# adc.net
KiCad netlist of a schematic drawn in EAGLE
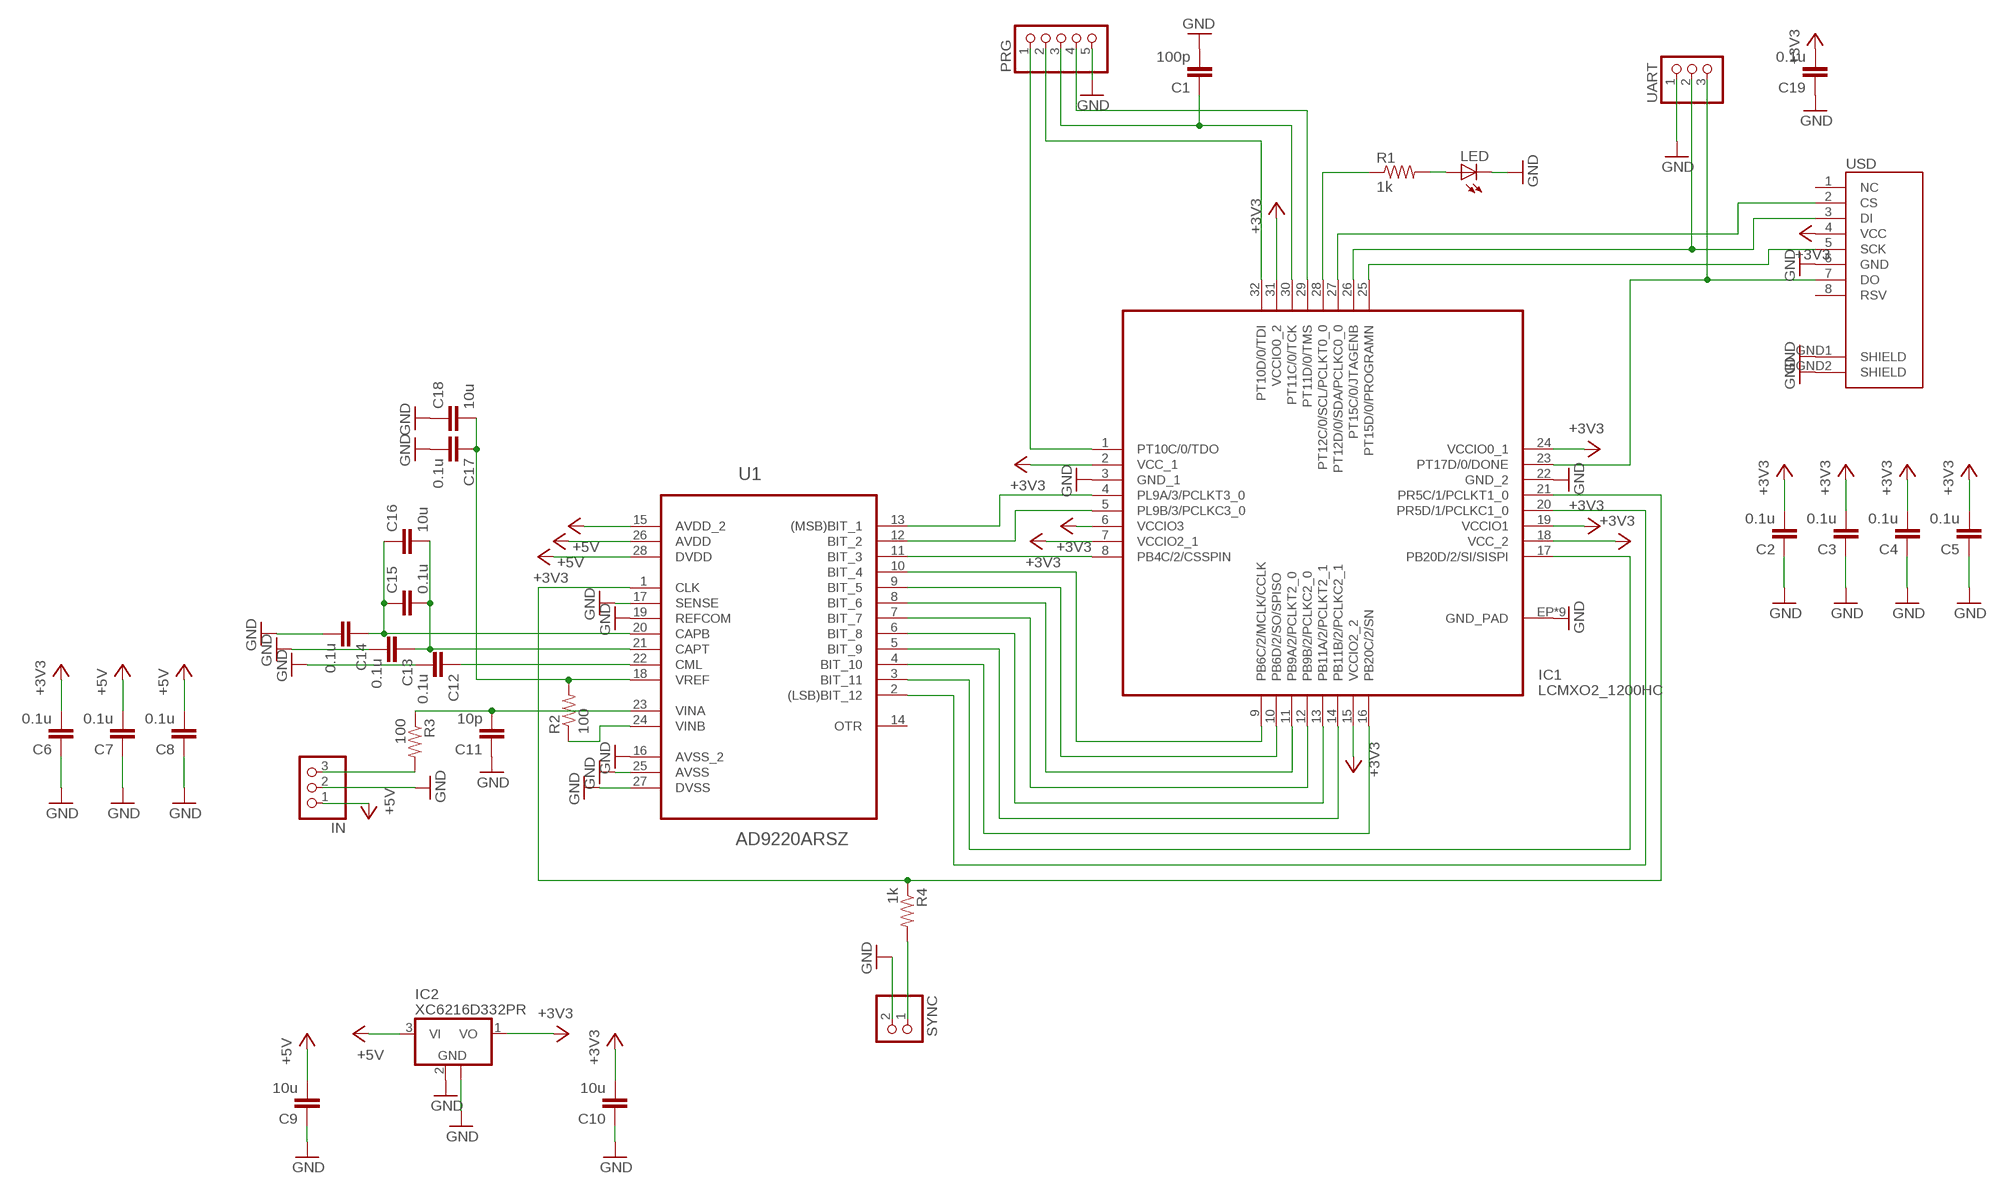
[diagram p0: schematic, sheet 1]

(export (version "E")
  (design (tool "Eeschema 10.0.6"))
  (components
    (comp (ref "C1")
      (value "100p")
      (footprint "eagle-import:C0603")
      (libsource (lib "eagle-import") (part "C-EUC0603"))
    )
    (comp (ref "C2")
      (value "0.1u")
      (footprint "eagle-import:C0603")
      (libsource (lib "eagle-import") (part "C-EUC0603"))
    )
    (comp (ref "C3")
      (value "0.1u")
      (footprint "eagle-import:C0603")
      (libsource (lib "eagle-import") (part "C-EUC0603"))
    )
    (comp (ref "C4")
      (value "0.1u")
      (footprint "eagle-import:C0603")
      (libsource (lib "eagle-import") (part "C-EUC0603"))
    )
    (comp (ref "C5")
      (value "0.1u")
      (footprint "eagle-import:C0603")
      (libsource (lib "eagle-import") (part "C-EUC0603"))
    )
    (comp (ref "C6")
      (value "0.1u")
      (footprint "eagle-import:C0603")
      (libsource (lib "eagle-import") (part "C-EUC0603"))
    )
    (comp (ref "C7")
      (value "0.1u")
      (footprint "eagle-import:C0603")
      (libsource (lib "eagle-import") (part "C-EUC0603"))
    )
    (comp (ref "C8")
      (value "0.1u")
      (footprint "eagle-import:C0603")
      (libsource (lib "eagle-import") (part "C-EUC0603"))
    )
    (comp (ref "C9")
      (value "10u")
      (footprint "eagle-import:C1206")
      (libsource (lib "eagle-import") (part "C-EUC1206"))
    )
    (comp (ref "C10")
      (value "10u")
      (footprint "eagle-import:C1206")
      (libsource (lib "eagle-import") (part "C-EUC1206"))
    )
    (comp (ref "C11")
      (value "10p")
      (footprint "eagle-import:C0603")
      (libsource (lib "eagle-import") (part "C-EUC0603"))
    )
    (comp (ref "C12")
      (value "0.1u")
      (footprint "eagle-import:C0603")
      (libsource (lib "eagle-import") (part "C-EUC0603"))
    )
    (comp (ref "C13")
      (value "0.1u")
      (footprint "eagle-import:C0603")
      (libsource (lib "eagle-import") (part "C-EUC0603"))
    )
    (comp (ref "C14")
      (value "0.1u")
      (footprint "eagle-import:C0603")
      (libsource (lib "eagle-import") (part "C-EUC0603"))
    )
    (comp (ref "C15")
      (value "0.1u")
      (footprint "eagle-import:C0603")
      (libsource (lib "eagle-import") (part "C-EUC0603"))
    )
    (comp (ref "C16")
      (value "10u")
      (footprint "eagle-import:C1206")
      (libsource (lib "eagle-import") (part "C-EUC1206"))
    )
    (comp (ref "C17")
      (value "0.1u")
      (footprint "eagle-import:C0603")
      (libsource (lib "eagle-import") (part "C-EUC0603"))
    )
    (comp (ref "C18")
      (value "10u")
      (footprint "eagle-import:C1206")
      (libsource (lib "eagle-import") (part "C-EUC1206"))
    )
    (comp (ref "C19")
      (value "0.1u")
      (footprint "eagle-import:C0603")
      (libsource (lib "eagle-import") (part "C-EUC0603"))
    )
    (comp (ref "IC1")
      (value "LCMXO2_1200HC")
      (footprint "eagle-import:QFN32_5X5")
      (libsource (lib "eagle-import") (part "LCMXO2_1200HC"))
    )
    (comp (ref "IC2")
      (value "XC6216D332PR")
      (footprint "eagle-import:SOT89")
      (libsource (lib "eagle-import") (part "78LF05"))
    )
    (comp (ref "IN")
      (value "PINHD-1X3")
      (footprint "eagle-import:1X03")
      (libsource (lib "eagle-import") (part "PINHD-1X3"))
    )
    (comp (ref "LED")
      (value "LEDSML0805")
      (footprint "eagle-import:SML0805")
      (libsource (lib "eagle-import") (part "LEDSML0805"))
    )
    (comp (ref "PRG")
      (value "PINHD-1X5")
      (footprint "eagle-import:1X05")
      (libsource (lib "eagle-import") (part "PINHD-1X5"))
    )
    (comp (ref "R1")
      (value "1k")
      (footprint "eagle-import:R0603")
      (libsource (lib "eagle-import") (part "R-US_R0603"))
    )
    (comp (ref "R2")
      (value "100")
      (footprint "eagle-import:R0603")
      (libsource (lib "eagle-import") (part "R-US_R0603"))
    )
    (comp (ref "R3")
      (value "100")
      (footprint "eagle-import:R0603")
      (libsource (lib "eagle-import") (part "R-US_R0603"))
    )
    (comp (ref "R4")
      (value "1k")
      (footprint "eagle-import:R0603")
      (libsource (lib "eagle-import") (part "R-US_R0603"))
    )
    (comp (ref "SYNC")
      (value "PINHD-1X2")
      (footprint "eagle-import:1X02")
      (libsource (lib "eagle-import") (part "PINHD-1X2"))
    )
    (comp (ref "U1")
      (value "AD9220ARSZ")
      (footprint "eagle-import:SOP65P780X200-28N")
      (libsource (lib "eagle-import") (part "AD9220ARSZ"))
    )
    (comp (ref "UART")
      (value "PINHD-1X3")
      (footprint "eagle-import:1X03")
      (libsource (lib "eagle-import") (part "PINHD-1X3"))
    )
    (comp (ref "USD")
      (value "USD-SOCKETUSD")
      (footprint "eagle-import:USD-SOCKET-PP")
      (libsource (lib "eagle-import") (part "USD-SOCKETUSD"))
    )
  )
  (nets
    (net (code "1") (name "+3V3") (class "Default")
      (node (ref "C10") (pin "2") (pinfunction "2_2") (pintype "passive"))
      (node (ref "C19") (pin "2") (pinfunction "2_2") (pintype "passive"))
      (node (ref "C2") (pin "2") (pinfunction "2_2") (pintype "passive"))
      (node (ref "C3") (pin "2") (pinfunction "2_2") (pintype "passive"))
      (node (ref "C4") (pin "2") (pinfunction "2_2") (pintype "passive"))
      (node (ref "C5") (pin "2") (pinfunction "2_2") (pintype "passive"))
      (node (ref "C6") (pin "2") (pinfunction "2_2") (pintype "passive"))
      (node (ref "IC1") (pin "15") (pinfunction "VCCIO2_2_15") (pintype "power_in"))
      (node (ref "IC1") (pin "18") (pinfunction "VCC_2_18") (pintype "power_in"))
      (node (ref "IC1") (pin "19") (pinfunction "VCCIO1_19") (pintype "power_in"))
      (node (ref "IC1") (pin "2") (pinfunction "VCC_1_2") (pintype "power_in"))
      (node (ref "IC1") (pin "24") (pinfunction "VCCIO0_1_24") (pintype "bidirectional"))
      (node (ref "IC1") (pin "31") (pinfunction "VCCIO0_2_31") (pintype "power_in"))
      (node (ref "IC1") (pin "6") (pinfunction "VCCIO3_6") (pintype "power_in"))
      (node (ref "IC1") (pin "7") (pinfunction "VCCIO2_1_7") (pintype "power_in"))
      (node (ref "IC2") (pin "1") (pinfunction "VO_1") (pintype "passive"))
      (node (ref "U1") (pin "28") (pinfunction "DVDD_28") (pintype "power_in"))
      (node (ref "USD") (pin "4") (pinfunction "VCC_4") (pintype "bidirectional"))
    )
    (net (code "2") (name "+5V") (class "Default")
      (node (ref "C7") (pin "2") (pinfunction "2_2") (pintype "passive"))
      (node (ref "C8") (pin "2") (pinfunction "2_2") (pintype "passive"))
      (node (ref "C9") (pin "2") (pinfunction "2_2") (pintype "passive"))
      (node (ref "IC2") (pin "3") (pinfunction "VI_3") (pintype "input"))
      (node (ref "IN") (pin "1") (pinfunction "1_1") (pintype "passive"))
      (node (ref "U1") (pin "15") (pinfunction "AVDD_2_15") (pintype "power_in"))
      (node (ref "U1") (pin "26") (pinfunction "AVDD_26") (pintype "power_in"))
    )
    (net (code "3") (name "GND") (class "Default")
      (node (ref "C1") (pin "2") (pinfunction "2_2") (pintype "passive"))
      (node (ref "C10") (pin "1") (pinfunction "1_1") (pintype "passive"))
      (node (ref "C11") (pin "1") (pinfunction "1_1") (pintype "passive"))
      (node (ref "C12") (pin "2") (pinfunction "2_2") (pintype "passive"))
      (node (ref "C13") (pin "2") (pinfunction "2_2") (pintype "passive"))
      (node (ref "C14") (pin "2") (pinfunction "2_2") (pintype "passive"))
      (node (ref "C17") (pin "2") (pinfunction "2_2") (pintype "passive"))
      (node (ref "C18") (pin "1") (pinfunction "1_1") (pintype "passive"))
      (node (ref "C19") (pin "1") (pinfunction "1_1") (pintype "passive"))
      (node (ref "C2") (pin "1") (pinfunction "1_1") (pintype "passive"))
      (node (ref "C3") (pin "1") (pinfunction "1_1") (pintype "passive"))
      (node (ref "C4") (pin "1") (pinfunction "1_1") (pintype "passive"))
      (node (ref "C5") (pin "1") (pinfunction "1_1") (pintype "passive"))
      (node (ref "C6") (pin "1") (pinfunction "1_1") (pintype "passive"))
      (node (ref "C7") (pin "1") (pinfunction "1_1") (pintype "passive"))
      (node (ref "C8") (pin "1") (pinfunction "1_1") (pintype "passive"))
      (node (ref "C9") (pin "1") (pinfunction "1_1") (pintype "passive"))
      (node (ref "IC1") (pin "22") (pinfunction "GND_2_22") (pintype "power_in"))
      (node (ref "IC1") (pin "3") (pinfunction "GND_1_3") (pintype "power_in"))
      (node (ref "IC1") (pin "EP") (pinfunction "GND_PAD_EP") (pintype "power_in"))
      (node (ref "IC1") (pin "EP1") (pinfunction "GND_PAD_EP1") (pintype "power_in"))
      (node (ref "IC1") (pin "EP2") (pinfunction "GND_PAD_EP2") (pintype "power_in"))
      (node (ref "IC1") (pin "EP3") (pinfunction "GND_PAD_EP3") (pintype "power_in"))
      (node (ref "IC1") (pin "EP4") (pinfunction "GND_PAD_EP4") (pintype "power_in"))
      (node (ref "IC1") (pin "EP5") (pinfunction "GND_PAD_EP5") (pintype "power_in"))
      (node (ref "IC1") (pin "EP6") (pinfunction "GND_PAD_EP6") (pintype "power_in"))
      (node (ref "IC1") (pin "EP7") (pinfunction "GND_PAD_EP7") (pintype "power_in"))
      (node (ref "IC1") (pin "PAD") (pinfunction "GND_PAD_PAD") (pintype "power_in"))
      (node (ref "IC2") (pin "2") (pinfunction "GND_2") (pintype "passive"))
      (node (ref "IC2") (pin "2@1") (pinfunction "GND_2@1") (pintype "passive"))
      (node (ref "IN") (pin "2") (pinfunction "2_2") (pintype "passive"))
      (node (ref "LED") (pin "C") (pinfunction "C_C") (pintype "passive"))
      (node (ref "PRG") (pin "5") (pinfunction "5_5") (pintype "passive"))
      (node (ref "SYNC") (pin "2") (pinfunction "2_2") (pintype "passive"))
      (node (ref "U1") (pin "16") (pinfunction "AVSS_2_16") (pintype "passive"))
      (node (ref "U1") (pin "17") (pinfunction "SENSE_17") (pintype "input"))
      (node (ref "U1") (pin "19") (pinfunction "REFCOM_19") (pintype "input"))
      (node (ref "U1") (pin "25") (pinfunction "AVSS_25") (pintype "passive"))
      (node (ref "U1") (pin "27") (pinfunction "DVSS_27") (pintype "input"))
      (node (ref "UART") (pin "1") (pinfunction "1_1") (pintype "passive"))
      (node (ref "USD") (pin "6") (pinfunction "GND_6") (pintype "bidirectional"))
      (node (ref "USD") (pin "GND1") (pinfunction "SHIELD_GND1") (pintype "bidirectional"))
      (node (ref "USD") (pin "GND2") (pinfunction "SHIELD_GND2") (pintype "bidirectional"))
    )
    (net (code "4") (name "Net-(IC1-PB4C{slash}2{slash}CSSPIN)") (class "Default")
      (node (ref "IC1") (pin "8") (pinfunction "PB4C/2/CSSPIN_8") (pintype "bidirectional"))
      (node (ref "U1") (pin "11") (pinfunction "BIT_3_11") (pintype "output"))
    )
    (net (code "5") (name "Net-(IC1-PB6C{slash}2{slash}MCLK{slash}CCLK)") (class "Default")
      (node (ref "IC1") (pin "9") (pinfunction "PB6C/2/MCLK/CCLK_9") (pintype "bidirectional"))
      (node (ref "U1") (pin "10") (pinfunction "BIT_4_10") (pintype "output"))
    )
    (net (code "6") (name "Net-(IC1-PB6D{slash}2{slash}SO{slash}SPISO)") (class "Default")
      (node (ref "IC1") (pin "10") (pinfunction "PB6D/2/SO/SPISO_10") (pintype "bidirectional"))
      (node (ref "U1") (pin "9") (pinfunction "BIT_5_9") (pintype "output"))
    )
    (net (code "7") (name "Net-(IC1-PB9A{slash}2{slash}PCLKT2_0)") (class "Default")
      (node (ref "IC1") (pin "11") (pinfunction "PB9A/2/PCLKT2_0_11") (pintype "bidirectional"))
      (node (ref "U1") (pin "8") (pinfunction "BIT_6_8") (pintype "output"))
    )
    (net (code "8") (name "Net-(IC1-PB9B{slash}2{slash}PCLKC2_0)") (class "Default")
      (node (ref "IC1") (pin "12") (pinfunction "PB9B/2/PCLKC2_0_12") (pintype "bidirectional"))
      (node (ref "U1") (pin "7") (pinfunction "BIT_7_7") (pintype "output"))
    )
    (net (code "9") (name "Net-(IC1-PB11A{slash}2{slash}PCLKT2_1)") (class "Default")
      (node (ref "IC1") (pin "13") (pinfunction "PB11A/2/PCLKT2_1_13") (pintype "bidirectional"))
      (node (ref "U1") (pin "6") (pinfunction "BIT_8_6") (pintype "output"))
    )
    (net (code "10") (name "Net-(IC1-PB11B{slash}2{slash}PCLKC2_1)") (class "Default")
      (node (ref "IC1") (pin "14") (pinfunction "PB11B/2/PCLKC2_1_14") (pintype "bidirectional"))
      (node (ref "U1") (pin "5") (pinfunction "BIT_9_5") (pintype "output"))
    )
    (net (code "11") (name "Net-(IC1-PB20C{slash}2{slash}SN)") (class "Default")
      (node (ref "IC1") (pin "16") (pinfunction "PB20C/2/SN_16") (pintype "bidirectional"))
      (node (ref "U1") (pin "4") (pinfunction "BIT_10_4") (pintype "output"))
    )
    (net (code "12") (name "Net-(IC1-PB20D{slash}2{slash}SI{slash}SISPI)") (class "Default")
      (node (ref "IC1") (pin "17") (pinfunction "PB20D/2/SI/SISPI_17") (pintype "bidirectional"))
      (node (ref "U1") (pin "3") (pinfunction "BIT_11_3") (pintype "output"))
    )
    (net (code "13") (name "Net-(IC1-PL9A{slash}3{slash}PCLKT3_0)") (class "Default")
      (node (ref "IC1") (pin "4") (pinfunction "PL9A/3/PCLKT3_0_4") (pintype "bidirectional"))
      (node (ref "U1") (pin "13") (pinfunction "(MSB)BIT_1_13") (pintype "output"))
    )
    (net (code "14") (name "Net-(IC1-PL9B{slash}3{slash}PCLKC3_0)") (class "Default")
      (node (ref "IC1") (pin "5") (pinfunction "PL9B/3/PCLKC3_0_5") (pintype "bidirectional"))
      (node (ref "U1") (pin "12") (pinfunction "BIT_2_12") (pintype "output"))
    )
    (net (code "15") (name "Net-(IC1-PR5C{slash}1{slash}PCLKT1_0)") (class "Default")
      (node (ref "IC1") (pin "21") (pinfunction "PR5C/1/PCLKT1_0_21") (pintype "bidirectional"))
      (node (ref "R4") (pin "1") (pinfunction "1_1") (pintype "passive"))
      (node (ref "U1") (pin "1") (pinfunction "CLK_1") (pintype "input"))
    )
    (net (code "16") (name "Net-(IC1-PR5D{slash}1{slash}PCLKC1_0)") (class "Default")
      (node (ref "IC1") (pin "20") (pinfunction "PR5D/1/PCLKC1_0_20") (pintype "bidirectional"))
      (node (ref "U1") (pin "2") (pinfunction "(LSB)BIT_12_2") (pintype "output"))
    )
    (net (code "17") (name "Net-(IC1-PT10C{slash}0{slash}TDO)") (class "Default")
      (node (ref "IC1") (pin "1") (pinfunction "PT10C/0/TDO_1") (pintype "bidirectional"))
      (node (ref "PRG") (pin "1") (pinfunction "1_1") (pintype "passive"))
    )
    (net (code "18") (name "Net-(IC1-PT10D{slash}0{slash}TDI)") (class "Default")
      (node (ref "IC1") (pin "32") (pinfunction "PT10D/0/TDI_32") (pintype "bidirectional"))
      (node (ref "PRG") (pin "2") (pinfunction "2_2") (pintype "passive"))
    )
    (net (code "19") (name "Net-(IC1-PT11C{slash}0{slash}TCK)") (class "Default")
      (node (ref "C1") (pin "1") (pinfunction "1_1") (pintype "passive"))
      (node (ref "IC1") (pin "30") (pinfunction "PT11C/0/TCK_30") (pintype "bidirectional"))
      (node (ref "PRG") (pin "3") (pinfunction "3_3") (pintype "passive"))
    )
    (net (code "20") (name "Net-(IC1-PT11D{slash}0{slash}TMS)") (class "Default")
      (node (ref "IC1") (pin "29") (pinfunction "PT11D/0/TMS_29") (pintype "bidirectional"))
      (node (ref "PRG") (pin "4") (pinfunction "4_4") (pintype "passive"))
    )
    (net (code "21") (name "Net-(IC1-PT12C{slash}0{slash}SCL{slash}PCLKT0_0)") (class "Default")
      (node (ref "IC1") (pin "28") (pinfunction "PT12C/0/SCL/PCLKT0_0_28") (pintype "bidirectional"))
      (node (ref "R1") (pin "1") (pinfunction "1_1") (pintype "passive"))
    )
    (net (code "22") (name "Net-(IC1-PT12D{slash}0{slash}SDA{slash}PCLKC0_0)") (class "Default")
      (node (ref "IC1") (pin "27") (pinfunction "PT12D/0/SDA/PCLKC0_0_27") (pintype "bidirectional"))
      (node (ref "USD") (pin "2") (pinfunction "CS_2") (pintype "bidirectional"))
    )
    (net (code "23") (name "Net-(IC1-PT15C{slash}0{slash}JTAGENB)") (class "Default")
      (node (ref "IC1") (pin "26") (pinfunction "PT15C/0/JTAGENB_26") (pintype "bidirectional"))
      (node (ref "UART") (pin "2") (pinfunction "2_2") (pintype "passive"))
      (node (ref "USD") (pin "3") (pinfunction "DI_3") (pintype "bidirectional"))
    )
    (net (code "24") (name "Net-(IC1-PT15D{slash}0{slash}PROGRAMN)") (class "Default")
      (node (ref "IC1") (pin "25") (pinfunction "PT15D/0/PROGRAMN_25") (pintype "bidirectional"))
      (node (ref "USD") (pin "5") (pinfunction "SCK_5") (pintype "bidirectional"))
    )
    (net (code "25") (name "Net-(IC1-PT17D{slash}0{slash}DONE)") (class "Default")
      (node (ref "IC1") (pin "23") (pinfunction "PT17D/0/DONE_23") (pintype "power_in"))
      (node (ref "UART") (pin "3") (pinfunction "3_3") (pintype "passive"))
      (node (ref "USD") (pin "7") (pinfunction "DO_7") (pintype "bidirectional"))
    )
    (net (code "26") (name "Net-(IN-Pad3)") (class "Default")
      (node (ref "IN") (pin "3") (pinfunction "3_3") (pintype "passive"))
      (node (ref "R3") (pin "2") (pinfunction "2_2") (pintype "passive"))
    )
    (net (code "27") (name "Net-(LED-PadA)") (class "Default")
      (node (ref "LED") (pin "A") (pinfunction "A_A") (pintype "passive"))
      (node (ref "R1") (pin "2") (pinfunction "2_2") (pintype "passive"))
    )
    (net (code "28") (name "Net-(R4-Pad2)") (class "Default")
      (node (ref "R4") (pin "2") (pinfunction "2_2") (pintype "passive"))
      (node (ref "SYNC") (pin "1") (pinfunction "1_1") (pintype "passive"))
    )
    (net (code "29") (name "Net-(U1-CAPB)") (class "Default")
      (node (ref "C14") (pin "1") (pinfunction "1_1") (pintype "passive"))
      (node (ref "C15") (pin "1") (pinfunction "1_1") (pintype "passive"))
      (node (ref "C16") (pin "1") (pinfunction "1_1") (pintype "passive"))
      (node (ref "U1") (pin "20") (pinfunction "CAPB_20") (pintype "input"))
    )
    (net (code "30") (name "Net-(U1-CAPT)") (class "Default")
      (node (ref "C13") (pin "1") (pinfunction "1_1") (pintype "passive"))
      (node (ref "C15") (pin "2") (pinfunction "2_2") (pintype "passive"))
      (node (ref "C16") (pin "2") (pinfunction "2_2") (pintype "passive"))
      (node (ref "U1") (pin "21") (pinfunction "CAPT_21") (pintype "input"))
    )
    (net (code "31") (name "Net-(U1-CML)") (class "Default")
      (node (ref "C12") (pin "1") (pinfunction "1_1") (pintype "passive"))
      (node (ref "U1") (pin "22") (pinfunction "CML_22") (pintype "input"))
    )
    (net (code "32") (name "Net-(U1-VINA)") (class "Default")
      (node (ref "C11") (pin "2") (pinfunction "2_2") (pintype "passive"))
      (node (ref "R3") (pin "1") (pinfunction "1_1") (pintype "passive"))
      (node (ref "U1") (pin "23") (pinfunction "VINA_23") (pintype "input"))
    )
    (net (code "33") (name "Net-(U1-VINB)") (class "Default")
      (node (ref "R2") (pin "1") (pinfunction "1_1") (pintype "passive"))
      (node (ref "U1") (pin "24") (pinfunction "VINB_24") (pintype "input"))
    )
    (net (code "34") (name "Net-(U1-VREF)") (class "Default")
      (node (ref "C17") (pin "1") (pinfunction "1_1") (pintype "passive"))
      (node (ref "C18") (pin "2") (pinfunction "2_2") (pintype "passive"))
      (node (ref "R2") (pin "2") (pinfunction "2_2") (pintype "passive"))
      (node (ref "U1") (pin "18") (pinfunction "VREF_18") (pintype "bidirectional"))
    )
    (net (code "35") (name "unconnected-(U1-OTR-Pad14)") (class "Default")
      (node (ref "U1") (pin "14") (pinfunction "OTR_14") (pintype "output"))
    )
    (net (code "36") (name "unconnected-(USD-NC-Pad1)") (class "Default")
      (node (ref "USD") (pin "1") (pinfunction "NC_1") (pintype "bidirectional"))
    )
    (net (code "37") (name "unconnected-(USD-RSV-Pad8)") (class "Default")
      (node (ref "USD") (pin "8") (pinfunction "RSV_8") (pintype "bidirectional"))
    )
  )
)
